# Sheet1.net
KiCad netlist of a schematic drawn in Altium Designer
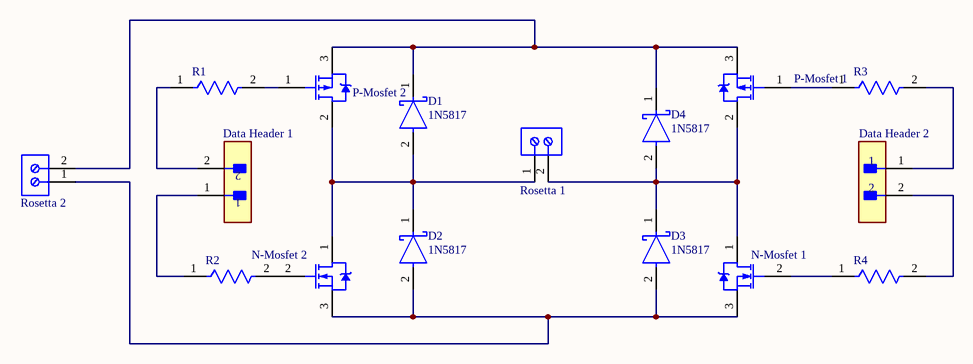
[diagram p0: Sheet1.SchDoc]

(export (version "E")
  (design (tool "Eeschema 10.0.6"))
  (components
    (comp (ref "D1")
      (value "1N5817")
      (footprint "FP-DO-41-MFG")
      (description "DIODE SCHOTTKY 20V 1A DO41")
      (libsource (lib "Altium Content Vault") (part "1d6ec82d83fb6aee721767c19dac4b9"))
    )
    (comp (ref "D2")
      (value "1N5817")
      (footprint "FP-DO-41-MFG")
      (description "DIODE SCHOTTKY 20V 1A DO41")
      (libsource (lib "Altium Content Vault") (part "1d6ec82d83fb6aee721767c19dac4b9"))
    )
    (comp (ref "D3")
      (value "1N5817")
      (footprint "FP-DO-41-MFG")
      (description "DIODE SCHOTTKY 20V 1A DO41")
      (libsource (lib "Altium Content Vault") (part "1d6ec82d83fb6aee721767c19dac4b9"))
    )
    (comp (ref "D4")
      (value "1N5817")
      (footprint "FP-DO-41-MFG")
      (description "DIODE SCHOTTKY 20V 1A DO41")
      (libsource (lib "Altium Content Vault") (part "1d6ec82d83fb6aee721767c19dac4b9"))
    )
    (comp (ref "Data Header 1")
      (value "M20-9990245")
      (footprint "FP-M20-9990245-MFG")
      (description "CONN HEADER VERT 2POS 2.54MM")
      (fields (field (name "VOLTAGE") "50V"))
      (libsource (lib "") (part "3bc925449376181038e59eaffc5286c_1"))
    )
    (comp (ref "Data Header 2")
      (value "M20-9990245")
      (footprint "FP-M20-9990245-MFG")
      (description "CONN HEADER VERT 2POS 2.54MM")
      (fields (field (name "VOLTAGE") "50V"))
      (libsource (lib "Altium Content Vault") (part "3bc925449376181038e59eaffc5286c"))
    )
    (comp (ref "N-Mosfet 1")
      (value "BS170")
      (footprint "ONSC-TO-92-3-29-11")
      (description "Small Signal MOSFET, 500 mA, 60 V, N-Channel, 3-Pin TO-92, Bulk Box")
      (fields (field (name "MANUFACTURER") "On Semiconductor"))
      (libsource (lib "Altium Content Vault") (part "ONSC-NMOS-D1G2S3-3"))
    )
    (comp (ref "N-Mosfet 2")
      (value "BS170")
      (footprint "ONSC-TO-92-3-29-11")
      (description "Small Signal MOSFET, 500 mA, 60 V, N-Channel, 3-Pin TO-92, Bulk Box")
      (fields (field (name "MANUFACTURER") "On Semiconductor"))
      (libsource (lib "Altium Content Vault") (part "ONSC-NMOS-D1G2S3-3"))
    )
    (comp (ref "P-Mosfet 1")
      (value "NTP2955")
      (footprint "ONSC-TO-220-3-221A-09_AA")
      (description "Power MOSFET, -60 V, -12 A, Single P-Channel, 3-Pin TO-220, Tube")
      (fields (field (name "MANUFACTURER") "On Semiconductor"))
      (libsource (lib "Altium Content Vault") (part "ONSC-PMOS-G1D2S3-3_B"))
    )
    (comp (ref "P-Mosfet 2")
      (value "NTP2955")
      (footprint "ONSC-TO-220-3-221A-09_AA")
      (description "Power MOSFET, -60 V, -12 A, Single P-Channel, 3-Pin TO-220, Tube")
      (fields (field (name "MANUFACTURER") "On Semiconductor"))
      (libsource (lib "Altium Content Vault") (part "ONSC-PMOS-G1D2S3-3_B"))
    )
    (comp (ref "R1")
      (value "H45K0BAA")
      (footprint "FP-H45K0BAA-MFG")
      (description "RES 5.00K OHM 1/2W 0.1% AXIAL")
      (fields (field (name "TOLERANCE") "0.1%"))
      (libsource (lib "Altium Content Vault") (part "1029c3af85768c4190bb7ad29bc67b5"))
    )
    (comp (ref "R2")
      (value "H45K0BAA")
      (footprint "FP-H45K0BAA-MFG")
      (description "RES 5.00K OHM 1/2W 0.1% AXIAL")
      (fields (field (name "TOLERANCE") "0.1%"))
      (libsource (lib "Altium Content Vault") (part "1029c3af85768c4190bb7ad29bc67b5"))
    )
    (comp (ref "R3")
      (value "H45K0BAA")
      (footprint "FP-H45K0BAA-MFG")
      (description "RES 5.00K OHM 1/2W 0.1% AXIAL")
      (fields (field (name "TOLERANCE") "0.1%"))
      (libsource (lib "Altium Content Vault") (part "1029c3af85768c4190bb7ad29bc67b5"))
    )
    (comp (ref "R4")
      (value "H45K0BAA")
      (footprint "FP-H45K0BAA-MFG")
      (description "RES 5.00K OHM 1/2W 0.1% AXIAL")
      (fields (field (name "TOLERANCE") "0.1%"))
      (libsource (lib "Altium Content Vault") (part "1029c3af85768c4190bb7ad29bc67b5"))
    )
    (comp (ref "Rosetta 1")
      (value "691214110002")
      (footprint "691214110002")
      (fields (field (name "VOLTAGE") "300V"))
      (libsource (lib "Altium Content Vault") (part "TBL - 1R - 02P - Screw"))
    )
    (comp (ref "Rosetta 2")
      (value "691214110002")
      (footprint "691214110002")
      (fields (field (name "VOLTAGE") "300V"))
      (libsource (lib "Altium Content Vault") (part "TBL - 1R - 02P - Screw"))
    )
  )
  (nets
    (net (code "2") (name "Net-(D1-A)") (class "Default")
      (node (ref "D1") (pin "2") (pinfunction "A_2") (pintype "passive"))
      (node (ref "D2") (pin "1") (pinfunction "C_1") (pintype "passive"))
      (node (ref "N-Mosfet 2") (pin "1") (pinfunction "D_1") (pintype "passive"))
      (node (ref "P-Mosfet 2") (pin "2") (pinfunction "D_2") (pintype "passive"))
      (node (ref "Rosetta 1") (pin "1") (pinfunction "1_1") (pintype "passive"))
    )
    (net (code "3") (name "Net-(D1-C)") (class "Default")
      (node (ref "D1") (pin "1") (pinfunction "C_1") (pintype "passive"))
      (node (ref "D4") (pin "1") (pinfunction "C_1") (pintype "passive"))
      (node (ref "P-Mosfet 1") (pin "3") (pinfunction "S_3") (pintype "passive"))
      (node (ref "P-Mosfet 2") (pin "3") (pinfunction "S_3") (pintype "passive"))
      (node (ref "Rosetta 2") (pin "2") (pinfunction "2_2") (pintype "passive"))
    )
    (net (code "4") (name "Net-(D2-A)") (class "Default")
      (node (ref "D2") (pin "2") (pinfunction "A_2") (pintype "passive"))
      (node (ref "D3") (pin "2") (pinfunction "A_2") (pintype "passive"))
      (node (ref "N-Mosfet 1") (pin "3") (pinfunction "S_3") (pintype "passive"))
      (node (ref "N-Mosfet 2") (pin "3") (pinfunction "S_3") (pintype "passive"))
      (node (ref "Rosetta 2") (pin "1") (pinfunction "1_1") (pintype "passive"))
    )
    (net (code "5") (name "Net-(D3-C)") (class "Default")
      (node (ref "D3") (pin "1") (pinfunction "C_1") (pintype "passive"))
      (node (ref "D4") (pin "2") (pinfunction "A_2") (pintype "passive"))
      (node (ref "N-Mosfet 1") (pin "1") (pinfunction "D_1") (pintype "passive"))
      (node (ref "P-Mosfet 1") (pin "2") (pinfunction "D_2") (pintype "passive"))
      (node (ref "Rosetta 1") (pin "2") (pinfunction "2_2") (pintype "passive"))
    )
    (net (code "6") (name "Net-(Data Header 1-Pad1)") (class "Default")
      (node (ref "Data Header 1") (pin "1") (pinfunction "1_1") (pintype "passive"))
      (node (ref "R2") (pin "1") (pinfunction "1_1") (pintype "passive"))
    )
    (net (code "7") (name "Net-(Data Header 1-Pad2)") (class "Default")
      (node (ref "Data Header 1") (pin "2") (pinfunction "2_2") (pintype "passive"))
      (node (ref "R1") (pin "1") (pinfunction "1_1") (pintype "passive"))
    )
    (net (code "8") (name "Net-(Data Header 2-Pad1)") (class "Default")
      (node (ref "Data Header 2") (pin "1") (pinfunction "1_1") (pintype "passive"))
      (node (ref "R3") (pin "2") (pinfunction "2_2") (pintype "passive"))
    )
    (net (code "9") (name "Net-(Data Header 2-Pad2)") (class "Default")
      (node (ref "Data Header 2") (pin "2") (pinfunction "2_2") (pintype "passive"))
      (node (ref "R4") (pin "2") (pinfunction "2_2") (pintype "passive"))
    )
    (net (code "10") (name "Net-(N-Mosfet 1-G)") (class "Default")
      (node (ref "N-Mosfet 1") (pin "2") (pinfunction "G_2") (pintype "passive"))
      (node (ref "R4") (pin "1") (pinfunction "1_1") (pintype "passive"))
    )
    (net (code "11") (name "Net-(N-Mosfet 2-G)") (class "Default")
      (node (ref "N-Mosfet 2") (pin "2") (pinfunction "G_2") (pintype "passive"))
      (node (ref "R2") (pin "2") (pinfunction "2_2") (pintype "passive"))
    )
    (net (code "12") (name "Net-(P-Mosfet 1-G)") (class "Default")
      (node (ref "P-Mosfet 1") (pin "1") (pinfunction "G_1") (pintype "passive"))
      (node (ref "R3") (pin "1") (pinfunction "1_1") (pintype "passive"))
    )
    (net (code "13") (name "Net-(P-Mosfet 2-G)") (class "Default")
      (node (ref "P-Mosfet 2") (pin "1") (pinfunction "G_1") (pintype "passive"))
      (node (ref "R1") (pin "2") (pinfunction "2_2") (pintype "passive"))
    )
  )
)
